# WL-ADC.net
KiCad netlist of a schematic drawn in Altium Designer
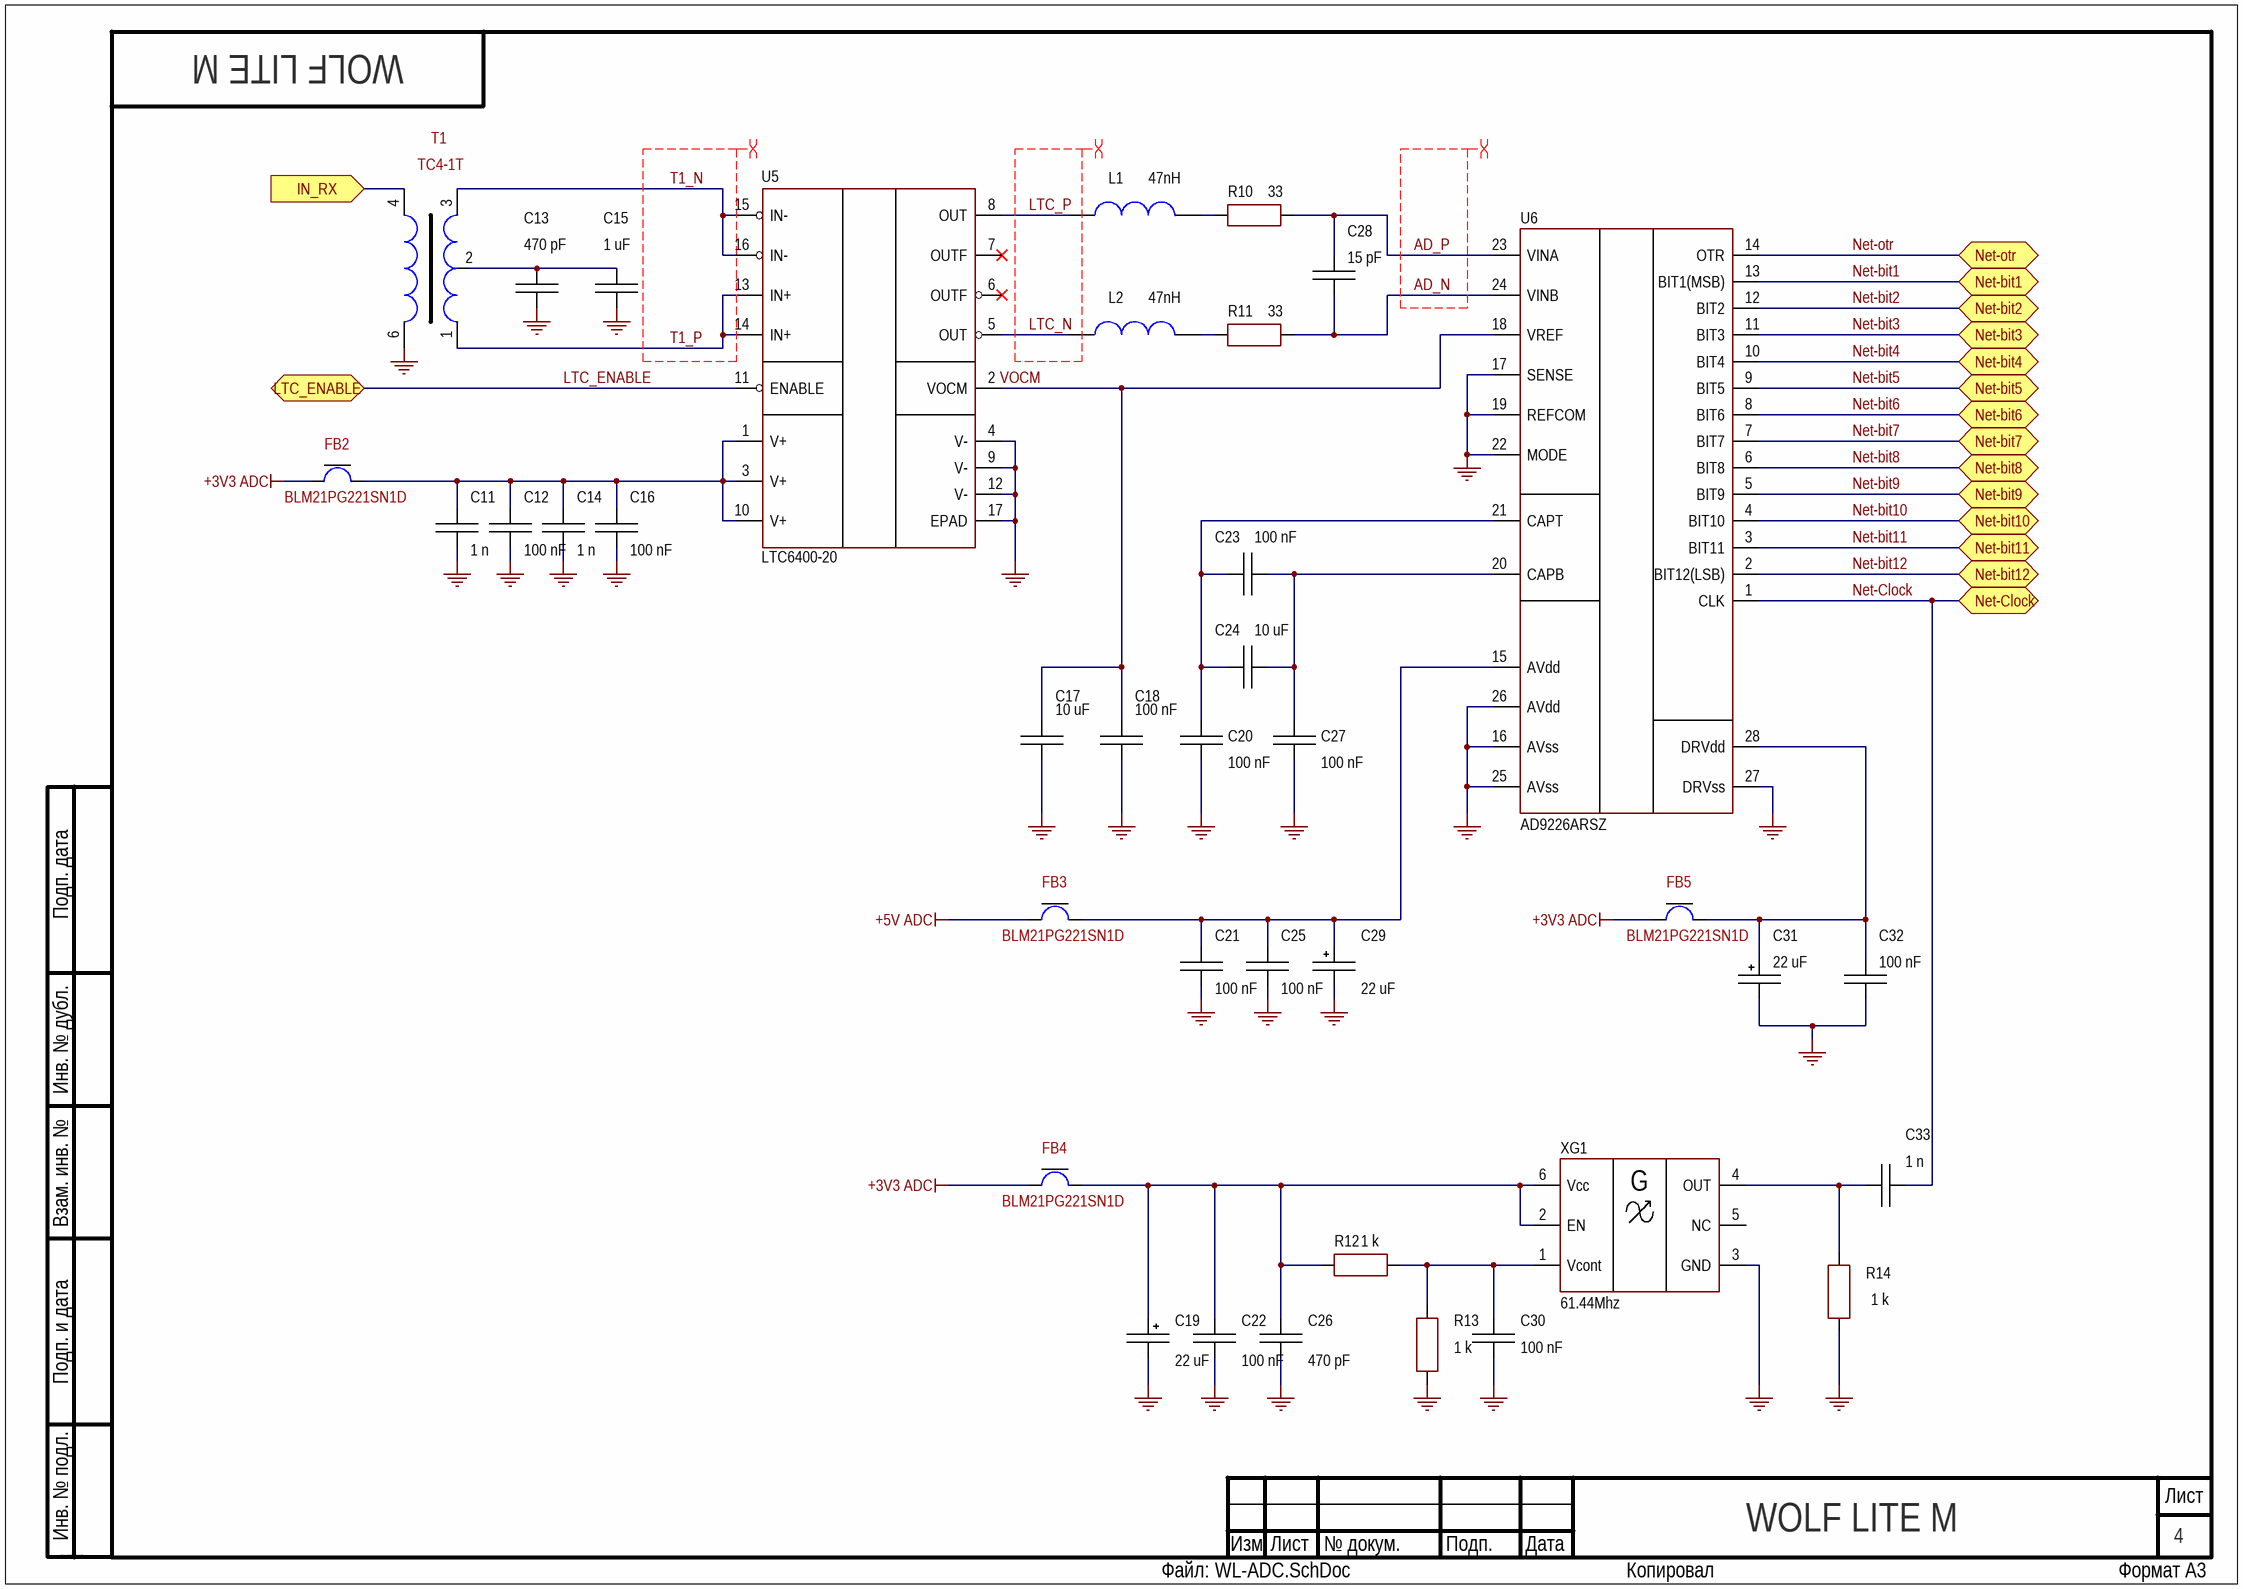
[diagram p0: WL-ADC.SchDoc]

(export (version "E")
  (design (tool "Eeschema 10.0.6"))
  (components
    (comp (ref "C11")
      (value "1 n")
      (footprint "C-0805-0.7")
      (fields
        (field (name "MANUFACTURER") "Yageo")
        (field (name "PART NUMBER") "CC0805JRNPO9BN102")
        (field (name "TOLERANCE") "±5%")
      )
      (libsource (lib "GOST") (part "Capacitor"))
    )
    (comp (ref "C12")
      (value "100 nF")
      (footprint "C-0805-0.95")
      (fields
        (field (name "MANUFACTURER") "Yageo")
        (field (name "PART NUMBER") "CC0805KRX7R9BB104")
        (field (name "TOLERANCE") "±10%")
      )
      (libsource (lib "GOST") (part "Capacitor"))
    )
    (comp (ref "C13")
      (value "470 pF")
      (footprint "C-0805-0.7")
      (fields
        (field (name "MANUFACTURER") "Yageo")
        (field (name "PART NUMBER") "CC0805JRNPO9BN471")
        (field (name "TOLERANCE") "±5%")
      )
      (libsource (lib "GOST") (part "Capacitor"))
    )
    (comp (ref "C14")
      (value "1 n")
      (footprint "C-0805-0.7")
      (fields
        (field (name "MANUFACTURER") "Yageo")
        (field (name "PART NUMBER") "CC0805JRNPO9BN102")
        (field (name "TOLERANCE") "±5%")
      )
      (libsource (lib "GOST") (part "Capacitor"))
    )
    (comp (ref "C15")
      (value "1 uF")
      (footprint "C-0805-1.25")
      (fields
        (field (name "MANUFACTURER") "Yageo")
        (field (name "PART NUMBER") "CC0805KKX7R9BB105")
        (field (name "TOLERANCE") "±10%")
      )
      (libsource (lib "GOST") (part "Capacitor"))
    )
    (comp (ref "C16")
      (value "100 nF")
      (footprint "C-0805-0.95")
      (fields
        (field (name "MANUFACTURER") "Yageo")
        (field (name "PART NUMBER") "CC0805KRX7R9BB104")
        (field (name "TOLERANCE") "±10%")
      )
      (libsource (lib "GOST") (part "Capacitor"))
    )
    (comp (ref "C17")
      (value "10 uF")
      (footprint "C-0805-1.25")
      (fields
        (field (name "MANUFACTURER") "Samsung Electro-Mechanics")
        (field (name "PART NUMBER") "CL21B106KOQNNNE")
        (field (name "TOLERANCE") "±10%")
      )
      (libsource (lib "GOST") (part "Capacitor"))
    )
    (comp (ref "C18")
      (value "100 nF")
      (footprint "C-0805-0.95")
      (fields
        (field (name "MANUFACTURER") "Yageo")
        (field (name "PART NUMBER") "CC0805KRX7R9BB104")
        (field (name "TOLERANCE") "±10%")
      )
      (libsource (lib "GOST") (part "Capacitor"))
    )
    (comp (ref "C19")
      (value "22 uF")
      (footprint "CAP-CASE B")
      (fields
        (field (name "MANUFACTURER") "Panasonic Electronic Components")
        (field (name "PART NUMBER") "EEE-1CA220WAR")
        (field (name "TOLERANCE") "±20%")
      )
      (libsource (lib "GOST") (part "Capacitor Polar"))
    )
    (comp (ref "C20")
      (value "100 nF")
      (footprint "C-0805-0.95")
      (fields
        (field (name "MANUFACTURER") "Yageo")
        (field (name "PART NUMBER") "CC0805KRX7R9BB104")
        (field (name "TOLERANCE") "±10%")
      )
      (libsource (lib "GOST") (part "Capacitor"))
    )
    (comp (ref "C21")
      (value "100 nF")
      (footprint "C-0805-0.95")
      (fields
        (field (name "MANUFACTURER") "Yageo")
        (field (name "PART NUMBER") "CC0805KRX7R9BB104")
        (field (name "TOLERANCE") "±10%")
      )
      (libsource (lib "GOST") (part "Capacitor"))
    )
    (comp (ref "C22")
      (value "100 nF")
      (footprint "C-0805-0.95")
      (fields
        (field (name "MANUFACTURER") "Yageo")
        (field (name "PART NUMBER") "CC0805KRX7R9BB104")
        (field (name "TOLERANCE") "±10%")
      )
      (libsource (lib "GOST") (part "Capacitor"))
    )
    (comp (ref "C23")
      (value "100 nF")
      (footprint "C-0805-0.95")
      (fields
        (field (name "MANUFACTURER") "Yageo")
        (field (name "PART NUMBER") "CC0805KRX7R9BB104")
        (field (name "TOLERANCE") "±10%")
      )
      (libsource (lib "GOST") (part "Capacitor"))
    )
    (comp (ref "C24")
      (value "10 uF")
      (footprint "C-0805-1.25")
      (fields
        (field (name "MANUFACTURER") "Samsung Electro-Mechanics")
        (field (name "PART NUMBER") "CL21B106KOQNNNE")
        (field (name "TOLERANCE") "±10%")
      )
      (libsource (lib "GOST") (part "Capacitor"))
    )
    (comp (ref "C25")
      (value "100 nF")
      (footprint "C-0805-0.95")
      (fields
        (field (name "MANUFACTURER") "Yageo")
        (field (name "PART NUMBER") "CC0805KRX7R9BB104")
        (field (name "TOLERANCE") "±10%")
      )
      (libsource (lib "GOST") (part "Capacitor"))
    )
    (comp (ref "C26")
      (value "470 pF")
      (footprint "C-0805-0.7")
      (fields
        (field (name "MANUFACTURER") "Yageo")
        (field (name "PART NUMBER") "CC0805JRNPO9BN471")
        (field (name "TOLERANCE") "±5%")
      )
      (libsource (lib "GOST") (part "Capacitor"))
    )
    (comp (ref "C27")
      (value "100 nF")
      (footprint "C-0805-0.95")
      (fields
        (field (name "MANUFACTURER") "Yageo")
        (field (name "PART NUMBER") "CC0805KRX7R9BB104")
        (field (name "TOLERANCE") "±10%")
      )
      (libsource (lib "GOST") (part "Capacitor"))
    )
    (comp (ref "C28")
      (value "15 pF")
      (footprint "C-0805-0.7")
      (fields
        (field (name "MANUFACTURER") "Yageo")
        (field (name "PART NUMBER") "CC0805JRNPO9BN150")
        (field (name "TOLERANCE") "±5%")
      )
      (libsource (lib "GOST") (part "Capacitor"))
    )
    (comp (ref "C29")
      (value "22 uF")
      (footprint "CAP-CASE B")
      (fields
        (field (name "MANUFACTURER") "Panasonic Electronic Components")
        (field (name "PART NUMBER") "EEE-1CA220WAR")
        (field (name "TOLERANCE") "±20%")
      )
      (libsource (lib "GOST") (part "Capacitor Polar"))
    )
    (comp (ref "C30")
      (value "100 nF")
      (footprint "C-0805-0.95")
      (fields
        (field (name "MANUFACTURER") "Yageo")
        (field (name "PART NUMBER") "CC0805KRX7R9BB104")
        (field (name "TOLERANCE") "±10%")
      )
      (libsource (lib "GOST") (part "Capacitor"))
    )
    (comp (ref "C31")
      (value "22 uF")
      (footprint "CAP-CASE B")
      (fields
        (field (name "MANUFACTURER") "Panasonic Electronic Components")
        (field (name "PART NUMBER") "EEE-1CA220WAR")
        (field (name "TOLERANCE") "±20%")
      )
      (libsource (lib "GOST") (part "Capacitor Polar"))
    )
    (comp (ref "C32")
      (value "100 nF")
      (footprint "C-0805-0.95")
      (fields
        (field (name "MANUFACTURER") "Yageo")
        (field (name "PART NUMBER") "CC0805KRX7R9BB104")
        (field (name "TOLERANCE") "±10%")
      )
      (libsource (lib "GOST") (part "Capacitor"))
    )
    (comp (ref "C33")
      (value "1 n")
      (footprint "C-0805-0.7")
      (fields
        (field (name "MANUFACTURER") "Yageo")
        (field (name "PART NUMBER") "CC0805JRNPO9BN102")
        (field (name "TOLERANCE") "±5%")
      )
      (libsource (lib "GOST") (part "Capacitor"))
    )
    (comp (ref "FB2")
      (value "BLM21PG221SN1D")
      (footprint "L-0805")
      (fields (field (name "MANUFACTURER") "Murata Electronics"))
      (libsource (lib "GOST") (part "Ferrite Bead"))
    )
    (comp (ref "FB3")
      (value "BLM21PG221SN1D")
      (footprint "L-0805")
      (fields (field (name "MANUFACTURER") "Murata Electronics"))
      (libsource (lib "GOST") (part "Ferrite Bead"))
    )
    (comp (ref "FB4")
      (value "BLM21PG221SN1D")
      (footprint "L-0805")
      (fields (field (name "MANUFACTURER") "Murata Electronics"))
      (libsource (lib "") (part "Ferrite Bead_1"))
    )
    (comp (ref "FB5")
      (value "BLM21PG221SN1D")
      (footprint "L-0805")
      (fields (field (name "MANUFACTURER") "Murata Electronics"))
      (libsource (lib "GOST") (part "Ferrite Bead"))
    )
    (comp (ref "L1")
      (value "47nH")
      (footprint "L-1210")
      (fields
        (field (name "MANUFACTURER") "FH(Guangdong Fenghua Advanced Tech)")
        (field (name "PART NUMBER") "FHW1210HC047JGT")
      )
      (libsource (lib "GOST") (part "Inductor"))
    )
    (comp (ref "L2")
      (value "47nH")
      (footprint "L-1210")
      (fields
        (field (name "MANUFACTURER") "FH(Guangdong Fenghua Advanced Tech)")
        (field (name "PART NUMBER") "FHW1210HC047JGT")
      )
      (libsource (lib "GOST") (part "Inductor"))
    )
    (comp (ref "R10")
      (value "33")
      (footprint "R-0805")
      (fields
        (field (name "MANUFACTURER") "Yageo")
        (field (name "PART NUMBER") "RC0805JR-0733RL")
        (field (name "POWER") "0,125 W")
      )
      (libsource (lib "") (part "Resistor_1"))
    )
    (comp (ref "R11")
      (value "33")
      (footprint "R-0805")
      (fields
        (field (name "MANUFACTURER") "Yageo")
        (field (name "PART NUMBER") "RC0805JR-0733RL")
        (field (name "POWER") "0,125 W")
      )
      (libsource (lib "") (part "Resistor_1"))
    )
    (comp (ref "R12")
      (value "1 k")
      (footprint "R-0805")
      (fields
        (field (name "MANUFACTURER") "Yageo")
        (field (name "PART NUMBER") "RC0805JR-071KL")
        (field (name "POWER") "0,125 W")
      )
      (libsource (lib "") (part "Resistor_1"))
    )
    (comp (ref "R13")
      (value "1 k")
      (footprint "R-0805")
      (fields
        (field (name "MANUFACTURER") "Yageo")
        (field (name "PART NUMBER") "RC0805JR-071KL")
        (field (name "POWER") "0,125 W")
      )
      (libsource (lib "") (part "Resistor_2"))
    )
    (comp (ref "R14")
      (value "1 k")
      (footprint "R-0805")
      (fields
        (field (name "MANUFACTURER") "Yageo")
        (field (name "PART NUMBER") "RC0805JR-071KL")
        (field (name "POWER") "0,125 W")
      )
      (libsource (lib "GOST") (part "Resistor"))
    )
    (comp (ref "T1")
      (value "TC4-1T")
      (footprint "TC4-1T")
      (fields (field (name "MANUFACTURER") "Mini-Circuits"))
      (libsource (lib "GOST") (part "TC4-1T"))
    )
    (comp (ref "U5")
      (value "LTC6400-20")
      (footprint "EQFN-16")
      (fields (field (name "MANUFACTURER") "Analog Devices Inc."))
      (libsource (lib "GOST") (part "LTC6400-20"))
    )
    (comp (ref "U6")
      (value "AD9226ARSZ")
      (footprint "SSOP-28")
      (description "IC ADC 12BIT")
      (fields (field (name "MANUFACTURER") "Analog Devices Inc."))
      (libsource (lib "GOST") (part "AD9226ARSZ"))
    )
    (comp (ref "XG1")
      (value "61.44Mhz")
      (footprint "VCXO")
      (fields (field (name "PART NUMBER") "VCXO"))
      (libsource (lib "GOST") (part "VCXO"))
    )
  )
  (nets
    (net (code "1") (name "+3V3 ADC") (class "Default")
      (node (ref "FB2") (pin "1") (pinfunction "1_1") (pintype "passive"))
      (node (ref "FB4") (pin "2") (pinfunction "2_2") (pintype "passive"))
      (node (ref "FB5") (pin "1") (pinfunction "1_1") (pintype "passive"))
    )
    (net (code "2") (name "+5V ADC") (class "Default")
      (node (ref "FB3") (pin "1") (pinfunction "1_1") (pintype "passive"))
    )
    (net (code "3") (name "/AD_N") (class "Default")
      (node (ref "C28") (pin "1") (pinfunction "1_1") (pintype "passive"))
      (node (ref "R11") (pin "2") (pinfunction "2_2") (pintype "passive"))
      (node (ref "U6") (pin "24") (pinfunction "VINB_24") (pintype "passive"))
    )
    (net (code "4") (name "/AD_P") (class "Default")
      (node (ref "C28") (pin "2") (pinfunction "2_2") (pintype "passive"))
      (node (ref "R10") (pin "2") (pinfunction "2_2") (pintype "passive"))
      (node (ref "U6") (pin "23") (pinfunction "VINA_23") (pintype "passive"))
    )
    (net (code "5") (name "/IN_RX") (class "Default")
      (node (ref "T1") (pin "4") (pinfunction "4_4") (pintype "passive"))
    )
    (net (code "6") (name "/LTC_ENABLE") (class "Default")
      (node (ref "U5") (pin "11") (pinfunction "ENABLE_11") (pintype "passive"))
    )
    (net (code "7") (name "/LTC_N") (class "Default")
      (node (ref "L2") (pin "1") (pinfunction "1_1") (pintype "passive"))
      (node (ref "U5") (pin "5") (pinfunction "OUT_5") (pintype "passive"))
    )
    (net (code "8") (name "/LTC_P") (class "Default")
      (node (ref "L1") (pin "1") (pinfunction "1_1") (pintype "passive"))
      (node (ref "U5") (pin "8") (pinfunction "OUT_8") (pintype "passive"))
    )
    (net (code "9") (name "/Net-Clock") (class "Default")
      (node (ref "C33") (pin "2") (pinfunction "2_2") (pintype "passive"))
      (node (ref "U6") (pin "1") (pinfunction "CLK_1") (pintype "passive"))
    )
    (net (code "10") (name "/Net-bit1") (class "Default")
      (node (ref "U6") (pin "13") (pinfunction "BIT1(MSB)_13") (pintype "passive"))
    )
    (net (code "11") (name "/Net-bit2") (class "Default")
      (node (ref "U6") (pin "12") (pinfunction "BIT2_12") (pintype "passive"))
    )
    (net (code "12") (name "/Net-bit3") (class "Default")
      (node (ref "U6") (pin "11") (pinfunction "BIT3_11") (pintype "passive"))
    )
    (net (code "13") (name "/Net-bit4") (class "Default")
      (node (ref "U6") (pin "10") (pinfunction "BIT4_10") (pintype "passive"))
    )
    (net (code "14") (name "/Net-bit5") (class "Default")
      (node (ref "U6") (pin "9") (pinfunction "BIT5_9") (pintype "passive"))
    )
    (net (code "15") (name "/Net-bit6") (class "Default")
      (node (ref "U6") (pin "8") (pinfunction "BIT6_8") (pintype "passive"))
    )
    (net (code "16") (name "/Net-bit7") (class "Default")
      (node (ref "U6") (pin "7") (pinfunction "BIT7_7") (pintype "passive"))
    )
    (net (code "17") (name "/Net-bit8") (class "Default")
      (node (ref "U6") (pin "6") (pinfunction "BIT8_6") (pintype "passive"))
    )
    (net (code "18") (name "/Net-bit9") (class "Default")
      (node (ref "U6") (pin "5") (pinfunction "BIT9_5") (pintype "passive"))
    )
    (net (code "19") (name "/Net-bit10") (class "Default")
      (node (ref "U6") (pin "4") (pinfunction "BIT10_4") (pintype "passive"))
    )
    (net (code "20") (name "/Net-bit11") (class "Default")
      (node (ref "U6") (pin "3") (pinfunction "BIT11_3") (pintype "passive"))
    )
    (net (code "21") (name "/Net-bit12") (class "Default")
      (node (ref "U6") (pin "2") (pinfunction "BIT12(LSB)_2") (pintype "passive"))
    )
    (net (code "22") (name "/Net-otr") (class "Default")
      (node (ref "U6") (pin "14") (pinfunction "OTR_14") (pintype "passive"))
    )
    (net (code "23") (name "/T1_N") (class "Default")
      (node (ref "T1") (pin "3") (pinfunction "3_3") (pintype "passive"))
      (node (ref "U5") (pin "15") (pinfunction "IN-_15") (pintype "passive"))
      (node (ref "U5") (pin "16") (pinfunction "IN-_16") (pintype "passive"))
    )
    (net (code "24") (name "/T1_P") (class "Default")
      (node (ref "T1") (pin "1") (pinfunction "1_1") (pintype "passive"))
      (node (ref "U5") (pin "13") (pinfunction "IN+_13") (pintype "passive"))
      (node (ref "U5") (pin "14") (pinfunction "IN+_14") (pintype "passive"))
    )
    (net (code "25") (name "/VOCM") (class "Default")
      (node (ref "C17") (pin "1") (pinfunction "1_1") (pintype "passive"))
      (node (ref "C18") (pin "2") (pinfunction "2_2") (pintype "passive"))
      (node (ref "U5") (pin "2") (pinfunction "VOCM_2") (pintype "passive"))
      (node (ref "U6") (pin "18") (pinfunction "VREF_18") (pintype "passive"))
    )
    (net (code "26") (name "GND") (class "Default")
      (node (ref "C11") (pin "1") (pinfunction "1_1") (pintype "passive"))
      (node (ref "C12") (pin "1") (pinfunction "1_1") (pintype "passive"))
      (node (ref "C13") (pin "2") (pinfunction "2_2") (pintype "passive"))
      (node (ref "C14") (pin "1") (pinfunction "1_1") (pintype "passive"))
      (node (ref "C15") (pin "1") (pinfunction "1_1") (pintype "passive"))
      (node (ref "C16") (pin "1") (pinfunction "1_1") (pintype "passive"))
      (node (ref "C17") (pin "2") (pinfunction "2_2") (pintype "passive"))
      (node (ref "C18") (pin "1") (pinfunction "1_1") (pintype "passive"))
      (node (ref "C19") (pin "2") (pinfunction "2_2") (pintype "passive"))
      (node (ref "C20") (pin "1") (pinfunction "1_1") (pintype "passive"))
      (node (ref "C21") (pin "1") (pinfunction "1_1") (pintype "passive"))
      (node (ref "C22") (pin "2") (pinfunction "2_2") (pintype "passive"))
      (node (ref "C25") (pin "1") (pinfunction "1_1") (pintype "passive"))
      (node (ref "C26") (pin "2") (pinfunction "2_2") (pintype "passive"))
      (node (ref "C27") (pin "1") (pinfunction "1_1") (pintype "passive"))
      (node (ref "C29") (pin "2") (pinfunction "2_2") (pintype "passive"))
      (node (ref "C30") (pin "2") (pinfunction "2_2") (pintype "passive"))
      (node (ref "C31") (pin "2") (pinfunction "2_2") (pintype "passive"))
      (node (ref "C32") (pin "1") (pinfunction "1_1") (pintype "passive"))
      (node (ref "R13") (pin "2") (pinfunction "2_2") (pintype "passive"))
      (node (ref "R14") (pin "1") (pinfunction "1_1") (pintype "passive"))
      (node (ref "T1") (pin "6") (pinfunction "6_6") (pintype "passive"))
      (node (ref "U5") (pin "12") (pinfunction "V-_12") (pintype "passive"))
      (node (ref "U5") (pin "17") (pinfunction "EPAD_17") (pintype "passive"))
      (node (ref "U5") (pin "4") (pinfunction "V-_4") (pintype "passive"))
      (node (ref "U5") (pin "9") (pinfunction "V-_9") (pintype "passive"))
      (node (ref "U6") (pin "16") (pinfunction "AVss_16") (pintype "passive"))
      (node (ref "U6") (pin "17") (pinfunction "SENSE_17") (pintype "passive"))
      (node (ref "U6") (pin "19") (pinfunction "REFCOM_19") (pintype "passive"))
      (node (ref "U6") (pin "22") (pinfunction "MODE_22") (pintype "passive"))
      (node (ref "U6") (pin "25") (pinfunction "AVss_25") (pintype "passive"))
      (node (ref "U6") (pin "26") (pinfunction "AVdd_26") (pintype "passive"))
      (node (ref "U6") (pin "27") (pinfunction "DRVss_27") (pintype "passive"))
      (node (ref "XG1") (pin "3") (pinfunction "GND_3") (pintype "passive"))
    )
    (net (code "27") (name "Net-(C11-Pad2)") (class "Default")
      (node (ref "C11") (pin "2") (pinfunction "2_2") (pintype "passive"))
      (node (ref "C12") (pin "2") (pinfunction "2_2") (pintype "passive"))
      (node (ref "C14") (pin "2") (pinfunction "2_2") (pintype "passive"))
      (node (ref "C16") (pin "2") (pinfunction "2_2") (pintype "passive"))
      (node (ref "FB2") (pin "2") (pinfunction "2_2") (pintype "passive"))
      (node (ref "U5") (pin "1") (pinfunction "V+_1") (pintype "passive"))
      (node (ref "U5") (pin "10") (pinfunction "V+_10") (pintype "passive"))
      (node (ref "U5") (pin "3") (pinfunction "V+_3") (pintype "passive"))
    )
    (net (code "28") (name "Net-(C13-Pad1)") (class "Default")
      (node (ref "C13") (pin "1") (pinfunction "1_1") (pintype "passive"))
      (node (ref "C15") (pin "2") (pinfunction "2_2") (pintype "passive"))
      (node (ref "T1") (pin "2") (pinfunction "2_2") (pintype "passive"))
    )
    (net (code "29") (name "Net-(C21-Pad2)") (class "Default")
      (node (ref "C21") (pin "2") (pinfunction "2_2") (pintype "passive"))
      (node (ref "C25") (pin "2") (pinfunction "2_2") (pintype "passive"))
      (node (ref "C29") (pin "1") (pinfunction "1_1") (pintype "passive"))
      (node (ref "FB3") (pin "2") (pinfunction "2_2") (pintype "passive"))
      (node (ref "U6") (pin "15") (pinfunction "AVdd_15") (pintype "passive"))
    )
    (net (code "30") (name "Net-(L1-Pad2)") (class "Default")
      (node (ref "L1") (pin "2") (pinfunction "2_2") (pintype "passive"))
      (node (ref "R10") (pin "1") (pinfunction "1_1") (pintype "passive"))
    )
    (net (code "31") (name "Net-(L2-Pad2)") (class "Default")
      (node (ref "L2") (pin "2") (pinfunction "2_2") (pintype "passive"))
      (node (ref "R11") (pin "1") (pinfunction "1_1") (pintype "passive"))
    )
    (net (code "32") (name "Net-(U6-CAPB)") (class "Default")
      (node (ref "C23") (pin "2") (pinfunction "2_2") (pintype "passive"))
      (node (ref "C24") (pin "2") (pinfunction "2_2") (pintype "passive"))
      (node (ref "C27") (pin "2") (pinfunction "2_2") (pintype "passive"))
      (node (ref "U6") (pin "20") (pinfunction "CAPB_20") (pintype "passive"))
    )
    (net (code "33") (name "Net-(U6-CAPT)") (class "Default")
      (node (ref "C20") (pin "2") (pinfunction "2_2") (pintype "passive"))
      (node (ref "C23") (pin "1") (pinfunction "1_1") (pintype "passive"))
      (node (ref "C24") (pin "1") (pinfunction "1_1") (pintype "passive"))
      (node (ref "U6") (pin "21") (pinfunction "CAPT_21") (pintype "passive"))
    )
    (net (code "34") (name "Net-(U6-DRVdd)") (class "Default")
      (node (ref "C31") (pin "1") (pinfunction "1_1") (pintype "passive"))
      (node (ref "C32") (pin "2") (pinfunction "2_2") (pintype "passive"))
      (node (ref "FB5") (pin "2") (pinfunction "2_2") (pintype "passive"))
      (node (ref "U6") (pin "28") (pinfunction "DRVdd_28") (pintype "passive"))
    )
    (net (code "35") (name "Net-(XG1-EN)") (class "Default")
      (node (ref "C19") (pin "1") (pinfunction "1_1") (pintype "passive"))
      (node (ref "C22") (pin "1") (pinfunction "1_1") (pintype "passive"))
      (node (ref "C26") (pin "1") (pinfunction "1_1") (pintype "passive"))
      (node (ref "FB4") (pin "1") (pinfunction "1_1") (pintype "passive"))
      (node (ref "R12") (pin "1") (pinfunction "1_1") (pintype "passive"))
      (node (ref "XG1") (pin "2") (pinfunction "EN_2") (pintype "passive"))
      (node (ref "XG1") (pin "6") (pinfunction "Vcc_6") (pintype "passive"))
    )
    (net (code "36") (name "Net-(XG1-OUT)") (class "Default")
      (node (ref "C33") (pin "1") (pinfunction "1_1") (pintype "passive"))
      (node (ref "R14") (pin "2") (pinfunction "2_2") (pintype "passive"))
      (node (ref "XG1") (pin "4") (pinfunction "OUT_4") (pintype "passive"))
    )
    (net (code "37") (name "Net-(XG1-Vcont)") (class "Default")
      (node (ref "C30") (pin "1") (pinfunction "1_1") (pintype "passive"))
      (node (ref "R12") (pin "2") (pinfunction "2_2") (pintype "passive"))
      (node (ref "R13") (pin "1") (pinfunction "1_1") (pintype "passive"))
      (node (ref "XG1") (pin "1") (pinfunction "Vcont_1") (pintype "passive"))
    )
    (net (code "38") (name "unconnected-(U5-OUTF-Pad6)") (class "Default")
      (node (ref "U5") (pin "6") (pinfunction "OUTF_6") (pintype "passive+no_connect"))
    )
    (net (code "39") (name "unconnected-(U5-OUTF-Pad7)") (class "Default")
      (node (ref "U5") (pin "7") (pinfunction "OUTF_7") (pintype "passive+no_connect"))
    )
    (net (code "40") (name "unconnected-(XG1-NC-Pad5)") (class "Default")
      (node (ref "XG1") (pin "5") (pinfunction "NC_5") (pintype "passive"))
    )
  )
)
